# Pi3_Analog_hat.net
KiCad netlist of a schematic drawn in EAGLE
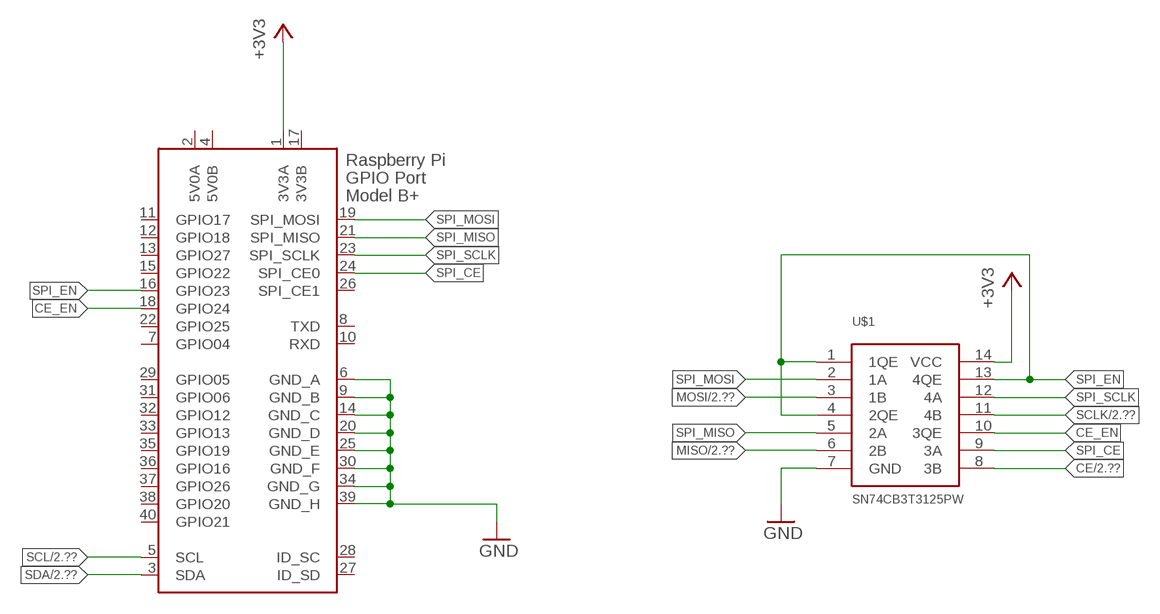
[diagram p0: schematic, sheet 1]
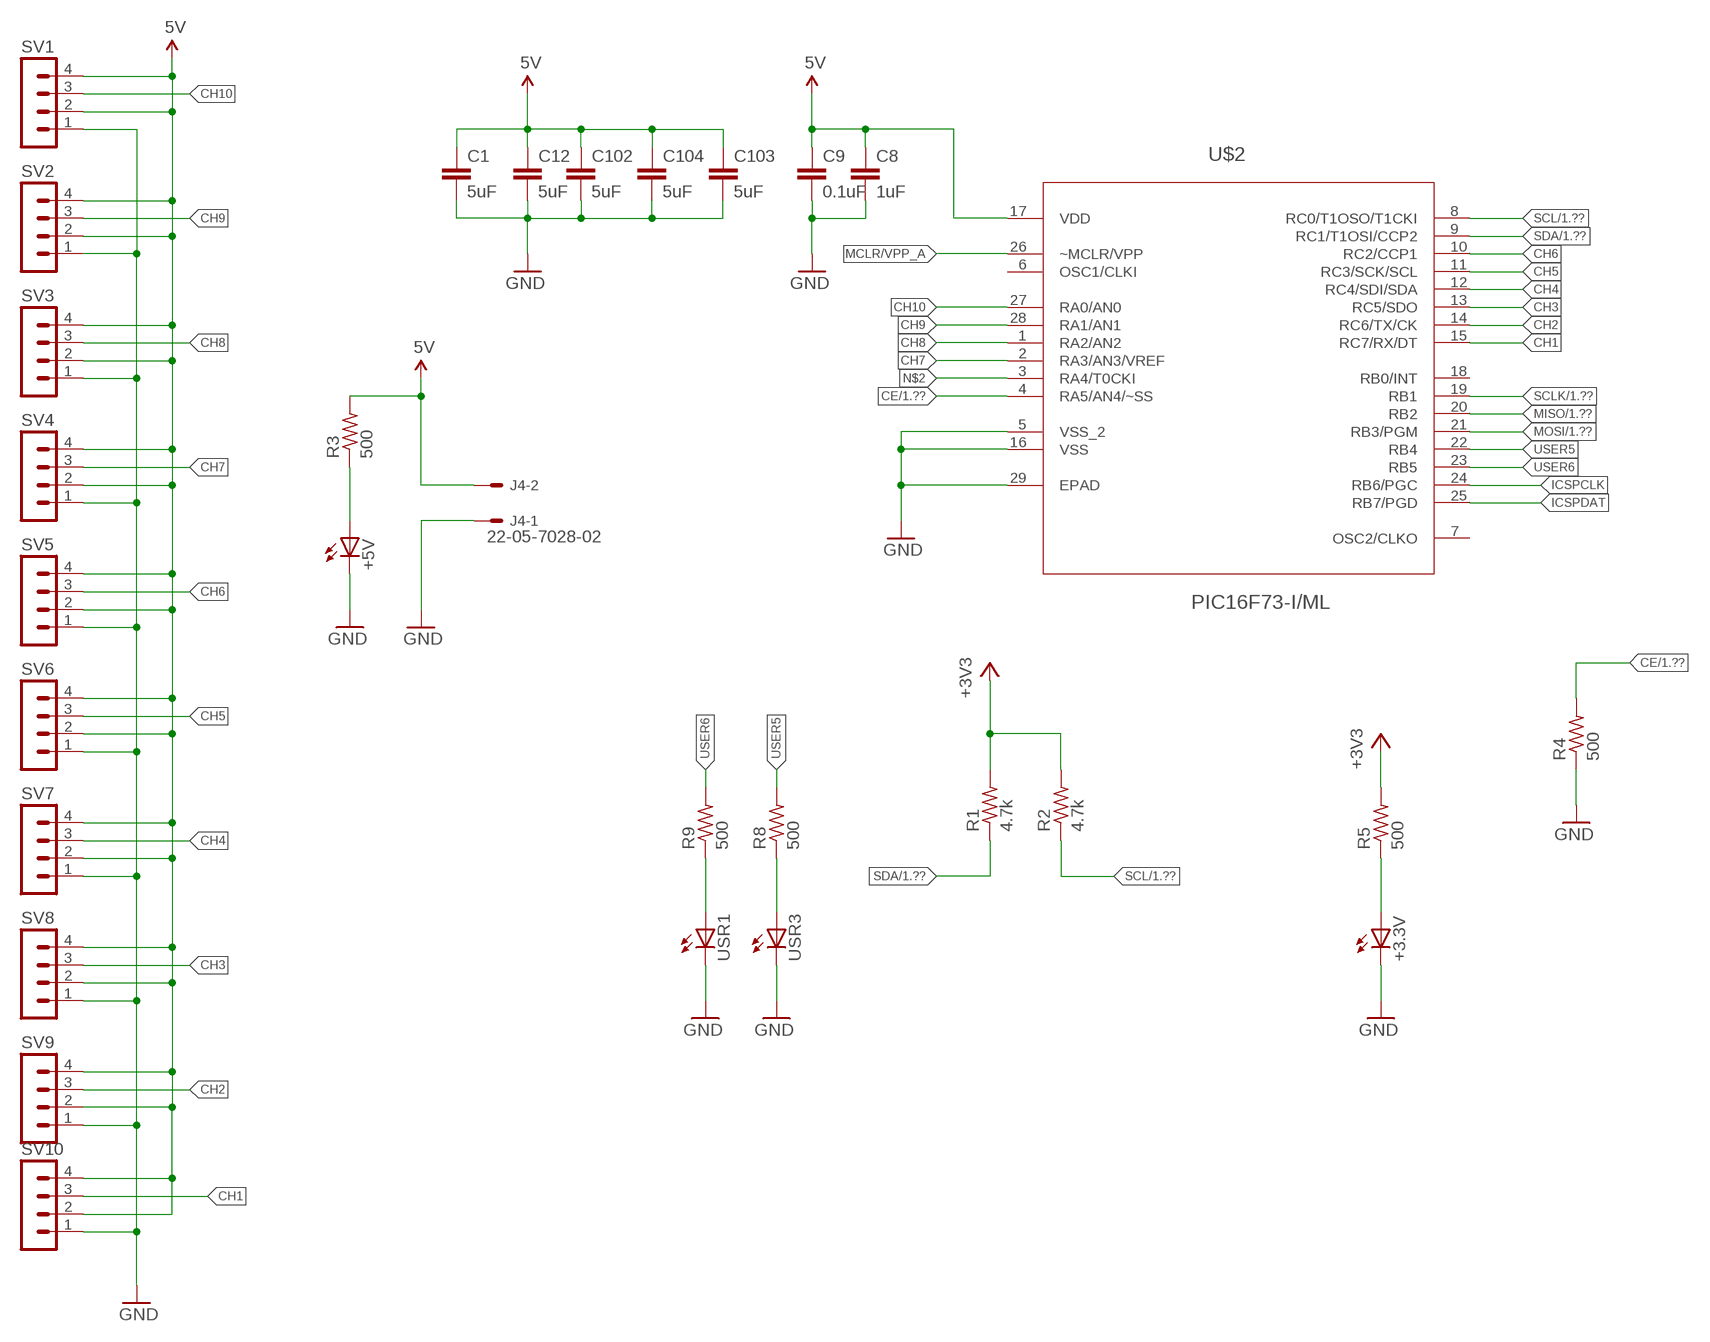
[diagram p1: schematic, sheet 2]

(export (version "E")
  (design (tool "Eeschema 10.0.6"))
  (components
    (comp (ref "+3.3V")
      (value "LEDCHIP-LED0603")
      (footprint "eagle-import:CHIP-LED0603")
      (libsource (lib "eagle-import") (part "LEDCHIP-LED0603"))
    )
    (comp (ref "+5V")
      (value "LEDCHIP-LED0603")
      (footprint "eagle-import:CHIP-LED0603")
      (libsource (lib "eagle-import") (part "LEDCHIP-LED0603"))
    )
    (comp (ref "C1")
      (value "5uF")
      (footprint "eagle-import:C0402")
      (libsource (lib "eagle-import") (part "C-EUC0402"))
    )
    (comp (ref "C8")
      (value "1uF")
      (footprint "eagle-import:C0402")
      (libsource (lib "eagle-import") (part "C-EUC0402"))
    )
    (comp (ref "C9")
      (value "0.1uF")
      (footprint "eagle-import:C0402")
      (libsource (lib "eagle-import") (part "C-EUC0402"))
    )
    (comp (ref "C12")
      (value "5uF")
      (footprint "eagle-import:C0402")
      (libsource (lib "eagle-import") (part "C-EUC0402"))
    )
    (comp (ref "C102")
      (value "5uF")
      (footprint "eagle-import:C0402")
      (libsource (lib "eagle-import") (part "C-EUC0402"))
    )
    (comp (ref "C103")
      (value "5uF")
      (footprint "eagle-import:C0402")
      (libsource (lib "eagle-import") (part "C-EUC0402"))
    )
    (comp (ref "C104")
      (value "5uF")
      (footprint "eagle-import:C0402")
      (libsource (lib "eagle-import") (part "C-EUC0402"))
    )
    (comp (ref "J4")
      (value "22-05-7028-02")
      (footprint "eagle-import:7395-02")
      (libsource (lib "eagle-import") (part "22-?-0205-7028"))
    )
    (comp (ref "R1")
      (value "4.7k")
      (footprint "eagle-import:R0402")
      (libsource (lib "eagle-import") (part "R-US_R0402"))
    )
    (comp (ref "R2")
      (value "4.7k")
      (footprint "eagle-import:R0402")
      (libsource (lib "eagle-import") (part "R-US_R0402"))
    )
    (comp (ref "R3")
      (value "500")
      (footprint "eagle-import:R0402")
      (libsource (lib "eagle-import") (part "R-US_R0402"))
    )
    (comp (ref "R4")
      (value "500")
      (footprint "eagle-import:R0402")
      (libsource (lib "eagle-import") (part "R-US_R0402"))
    )
    (comp (ref "R5")
      (value "500")
      (footprint "eagle-import:R0402")
      (libsource (lib "eagle-import") (part "R-US_R0402"))
    )
    (comp (ref "R8")
      (value "500")
      (footprint "eagle-import:R0402")
      (libsource (lib "eagle-import") (part "R-US_R0402"))
    )
    (comp (ref "R9")
      (value "500")
      (footprint "eagle-import:R0402")
      (libsource (lib "eagle-import") (part "R-US_R0402"))
    )
    (comp (ref "SV1")
      (value "MA04-1")
      (footprint "eagle-import:MA04-1")
      (libsource (lib "eagle-import") (part "MA04-1"))
    )
    (comp (ref "SV2")
      (value "MA04-1")
      (footprint "eagle-import:MA04-1")
      (libsource (lib "eagle-import") (part "MA04-1"))
    )
    (comp (ref "SV3")
      (value "MA04-1")
      (footprint "eagle-import:MA04-1")
      (libsource (lib "eagle-import") (part "MA04-1"))
    )
    (comp (ref "SV4")
      (value "MA04-1")
      (footprint "eagle-import:MA04-1")
      (libsource (lib "eagle-import") (part "MA04-1"))
    )
    (comp (ref "SV5")
      (value "MA04-1")
      (footprint "eagle-import:MA04-1")
      (libsource (lib "eagle-import") (part "MA04-1"))
    )
    (comp (ref "SV6")
      (value "MA04-1")
      (footprint "eagle-import:MA04-1")
      (libsource (lib "eagle-import") (part "MA04-1"))
    )
    (comp (ref "SV7")
      (value "MA04-1")
      (footprint "eagle-import:MA04-1")
      (libsource (lib "eagle-import") (part "MA04-1"))
    )
    (comp (ref "SV8")
      (value "MA04-1")
      (footprint "eagle-import:MA04-1")
      (libsource (lib "eagle-import") (part "MA04-1"))
    )
    (comp (ref "SV9")
      (value "MA04-1")
      (footprint "eagle-import:MA04-1")
      (libsource (lib "eagle-import") (part "MA04-1"))
    )
    (comp (ref "SV10")
      (value "MA04-1")
      (footprint "eagle-import:MA04-1")
      (libsource (lib "eagle-import") (part "MA04-1"))
    )
    (comp (ref "U$2")
      (value "PIC16F73-I/ML")
      (footprint "eagle-import:QFN65P600X600X100-28N")
      (libsource (lib "eagle-import") (part "PIC16F73-I/ML"))
    )
    (comp (ref "USR1")
      (value "LEDCHIP-LED0603")
      (footprint "eagle-import:CHIP-LED0603")
      (libsource (lib "eagle-import") (part "LEDCHIP-LED0603"))
    )
    (comp (ref "USR3")
      (value "LEDCHIP-LED0603")
      (footprint "eagle-import:CHIP-LED0603")
      (libsource (lib "eagle-import") (part "LEDCHIP-LED0603"))
    )
    (comp (ref "U$1")
      (value "SN74CB3T3125PW")
      (footprint "eagle-import:TSSOP-14")
      (libsource (lib "eagle-import") (part "SN74CB3T3125PW"))
    )
    (comp (ref "X1")
      (value "RASPI_BOARD_B+#_HD")
      (footprint "eagle-import:RASPI_BOARD_B+HAT_DF")
      (libsource (lib "eagle-import") (part "RASPI_BOARD_B+#_HD"))
    )
  )
  (nets
    (net (code "1") (name "+3V3") (class "Default")
      (node (ref "R1") (pin "2") (pinfunction "2_2") (pintype "passive"))
      (node (ref "R2") (pin "2") (pinfunction "2_2") (pintype "passive"))
      (node (ref "R5") (pin "2") (pinfunction "2_2") (pintype "passive"))
      (node (ref "U$1") (pin "14") (pinfunction "VCC_14") (pintype "bidirectional"))
      (node (ref "X1") (pin "1") (pinfunction "3V3A_1") (pintype "power_in"))
    )
    (net (code "2") (name "3V3B") (class "Default")
      (node (ref "X1") (pin "17") (pinfunction "3V3B_17") (pintype "power_in"))
    )
    (net (code "3") (name "5V") (class "Default")
      (node (ref "C1") (pin "1") (pinfunction "1_1") (pintype "passive"))
      (node (ref "C102") (pin "1") (pinfunction "1_1") (pintype "passive"))
      (node (ref "C103") (pin "1") (pinfunction "1_1") (pintype "passive"))
      (node (ref "C104") (pin "1") (pinfunction "1_1") (pintype "passive"))
      (node (ref "C12") (pin "1") (pinfunction "1_1") (pintype "passive"))
      (node (ref "C8") (pin "1") (pinfunction "1_1") (pintype "passive"))
      (node (ref "C9") (pin "1") (pinfunction "1_1") (pintype "passive"))
      (node (ref "J4") (pin "2") (pinfunction "S_2") (pintype "passive"))
      (node (ref "R3") (pin "2") (pinfunction "2_2") (pintype "passive"))
      (node (ref "SV1") (pin "2") (pinfunction "2_2") (pintype "passive"))
      (node (ref "SV1") (pin "4") (pinfunction "4_4") (pintype "passive"))
      (node (ref "SV10") (pin "2") (pinfunction "2_2") (pintype "passive"))
      (node (ref "SV10") (pin "4") (pinfunction "4_4") (pintype "passive"))
      (node (ref "SV2") (pin "2") (pinfunction "2_2") (pintype "passive"))
      (node (ref "SV2") (pin "4") (pinfunction "4_4") (pintype "passive"))
      (node (ref "SV3") (pin "2") (pinfunction "2_2") (pintype "passive"))
      (node (ref "SV3") (pin "4") (pinfunction "4_4") (pintype "passive"))
      (node (ref "SV4") (pin "2") (pinfunction "2_2") (pintype "passive"))
      (node (ref "SV4") (pin "4") (pinfunction "4_4") (pintype "passive"))
      (node (ref "SV5") (pin "2") (pinfunction "2_2") (pintype "passive"))
      (node (ref "SV5") (pin "4") (pinfunction "4_4") (pintype "passive"))
      (node (ref "SV6") (pin "2") (pinfunction "2_2") (pintype "passive"))
      (node (ref "SV6") (pin "4") (pinfunction "4_4") (pintype "passive"))
      (node (ref "SV7") (pin "2") (pinfunction "2_2") (pintype "passive"))
      (node (ref "SV7") (pin "4") (pinfunction "4_4") (pintype "passive"))
      (node (ref "SV8") (pin "2") (pinfunction "2_2") (pintype "passive"))
      (node (ref "SV8") (pin "4") (pinfunction "4_4") (pintype "passive"))
      (node (ref "SV9") (pin "2") (pinfunction "2_2") (pintype "passive"))
      (node (ref "SV9") (pin "4") (pinfunction "4_4") (pintype "passive"))
      (node (ref "U$2") (pin "17") (pinfunction "VDD_17") (pintype "power_in"))
    )
    (net (code "4") (name "5V0A") (class "Default")
      (node (ref "X1") (pin "2") (pinfunction "5V0A_2") (pintype "power_in"))
    )
    (net (code "5") (name "5V0B") (class "Default")
      (node (ref "X1") (pin "4") (pinfunction "5V0B_4") (pintype "power_in"))
    )
    (net (code "6") (name "CE") (class "Default")
      (node (ref "R4") (pin "2") (pinfunction "2_2") (pintype "passive"))
      (node (ref "U$1") (pin "8") (pinfunction "3B_8") (pintype "bidirectional"))
      (node (ref "U$2") (pin "4") (pinfunction "RA5/AN4/~{SS}_4") (pintype "bidirectional"))
    )
    (net (code "7") (name "CE_EN") (class "Default")
      (node (ref "U$1") (pin "10") (pinfunction "3QE_10") (pintype "bidirectional"))
      (node (ref "X1") (pin "18") (pinfunction "GPIO24_18") (pintype "bidirectional"))
    )
    (net (code "8") (name "CH1") (class "Default")
      (node (ref "SV10") (pin "3") (pinfunction "3_3") (pintype "passive"))
      (node (ref "U$2") (pin "15") (pinfunction "RC7/RX/DT_15") (pintype "bidirectional"))
    )
    (net (code "9") (name "CH2") (class "Default")
      (node (ref "SV9") (pin "3") (pinfunction "3_3") (pintype "passive"))
      (node (ref "U$2") (pin "14") (pinfunction "RC6/TX/CK_14") (pintype "bidirectional"))
    )
    (net (code "10") (name "CH3") (class "Default")
      (node (ref "SV8") (pin "3") (pinfunction "3_3") (pintype "passive"))
      (node (ref "U$2") (pin "13") (pinfunction "RC5/SDO_13") (pintype "bidirectional"))
    )
    (net (code "11") (name "CH4") (class "Default")
      (node (ref "SV7") (pin "3") (pinfunction "3_3") (pintype "passive"))
      (node (ref "U$2") (pin "12") (pinfunction "RC4/SDI/SDA_12") (pintype "bidirectional"))
    )
    (net (code "12") (name "CH5") (class "Default")
      (node (ref "SV6") (pin "3") (pinfunction "3_3") (pintype "passive"))
      (node (ref "U$2") (pin "11") (pinfunction "RC3/SCK/SCL_11") (pintype "bidirectional"))
    )
    (net (code "13") (name "CH6") (class "Default")
      (node (ref "SV5") (pin "3") (pinfunction "3_3") (pintype "passive"))
      (node (ref "U$2") (pin "10") (pinfunction "RC2/CCP1_10") (pintype "bidirectional"))
    )
    (net (code "14") (name "CH7") (class "Default")
      (node (ref "SV4") (pin "3") (pinfunction "3_3") (pintype "passive"))
      (node (ref "U$2") (pin "2") (pinfunction "RA3/AN3/VREF_2") (pintype "bidirectional"))
    )
    (net (code "15") (name "CH8") (class "Default")
      (node (ref "SV3") (pin "3") (pinfunction "3_3") (pintype "passive"))
      (node (ref "U$2") (pin "1") (pinfunction "RA2/AN2_1") (pintype "bidirectional"))
    )
    (net (code "16") (name "CH9") (class "Default")
      (node (ref "SV2") (pin "3") (pinfunction "3_3") (pintype "passive"))
      (node (ref "U$2") (pin "28") (pinfunction "RA1/AN1_28") (pintype "bidirectional"))
    )
    (net (code "17") (name "CH10") (class "Default")
      (node (ref "SV1") (pin "3") (pinfunction "3_3") (pintype "passive"))
      (node (ref "U$2") (pin "27") (pinfunction "RA0/AN0_27") (pintype "bidirectional"))
    )
    (net (code "18") (name "GND") (class "Default")
      (node (ref "+3.3V") (pin "C") (pinfunction "C_C") (pintype "passive"))
      (node (ref "+5V") (pin "C") (pinfunction "C_C") (pintype "passive"))
      (node (ref "C1") (pin "2") (pinfunction "2_2") (pintype "passive"))
      (node (ref "C102") (pin "2") (pinfunction "2_2") (pintype "passive"))
      (node (ref "C103") (pin "2") (pinfunction "2_2") (pintype "passive"))
      (node (ref "C104") (pin "2") (pinfunction "2_2") (pintype "passive"))
      (node (ref "C12") (pin "2") (pinfunction "2_2") (pintype "passive"))
      (node (ref "C8") (pin "2") (pinfunction "2_2") (pintype "passive"))
      (node (ref "C9") (pin "2") (pinfunction "2_2") (pintype "passive"))
      (node (ref "J4") (pin "1") (pinfunction "S_1") (pintype "passive"))
      (node (ref "R4") (pin "1") (pinfunction "1_1") (pintype "passive"))
      (node (ref "SV1") (pin "1") (pinfunction "1_1") (pintype "passive"))
      (node (ref "SV10") (pin "1") (pinfunction "1_1") (pintype "passive"))
      (node (ref "SV2") (pin "1") (pinfunction "1_1") (pintype "passive"))
      (node (ref "SV3") (pin "1") (pinfunction "1_1") (pintype "passive"))
      (node (ref "SV4") (pin "1") (pinfunction "1_1") (pintype "passive"))
      (node (ref "SV5") (pin "1") (pinfunction "1_1") (pintype "passive"))
      (node (ref "SV6") (pin "1") (pinfunction "1_1") (pintype "passive"))
      (node (ref "SV7") (pin "1") (pinfunction "1_1") (pintype "passive"))
      (node (ref "SV8") (pin "1") (pinfunction "1_1") (pintype "passive"))
      (node (ref "SV9") (pin "1") (pinfunction "1_1") (pintype "passive"))
      (node (ref "U$1") (pin "7") (pinfunction "GND_7") (pintype "bidirectional"))
      (node (ref "U$2") (pin "16") (pinfunction "VSS_16") (pintype "power_in"))
      (node (ref "U$2") (pin "29") (pinfunction "EPAD_29") (pintype "passive"))
      (node (ref "U$2") (pin "5") (pinfunction "VSS_2_5") (pintype "power_in"))
      (node (ref "USR1") (pin "C") (pinfunction "C_C") (pintype "passive"))
      (node (ref "USR3") (pin "C") (pinfunction "C_C") (pintype "passive"))
      (node (ref "X1") (pin "14") (pinfunction "GND_C_14") (pintype "power_in"))
      (node (ref "X1") (pin "20") (pinfunction "GND_D_20") (pintype "power_in"))
      (node (ref "X1") (pin "25") (pinfunction "GND_E_25") (pintype "power_in"))
      (node (ref "X1") (pin "30") (pinfunction "GND_F_30") (pintype "power_in"))
      (node (ref "X1") (pin "34") (pinfunction "GND_G_34") (pintype "power_in"))
      (node (ref "X1") (pin "39") (pinfunction "GND_H_39") (pintype "power_in"))
      (node (ref "X1") (pin "6") (pinfunction "GND_A_6") (pintype "power_in"))
      (node (ref "X1") (pin "9") (pinfunction "GND_B_9") (pintype "power_in"))
    )
    (net (code "19") (name "ICSPCLK") (class "Default")
      (node (ref "U$2") (pin "24") (pinfunction "RB6/PGC_24") (pintype "bidirectional"))
    )
    (net (code "20") (name "ICSPDAT") (class "Default")
      (node (ref "U$2") (pin "25") (pinfunction "RB7/PGD_25") (pintype "bidirectional"))
    )
    (net (code "21") (name "MCLR{slash}VPP_A") (class "Default")
      (node (ref "U$2") (pin "26") (pinfunction "~{MCLR/VPP}_26") (pintype "input"))
    )
    (net (code "22") (name "MISO") (class "Default")
      (node (ref "U$1") (pin "6") (pinfunction "2B_6") (pintype "bidirectional"))
      (node (ref "U$2") (pin "20") (pinfunction "RB2_20") (pintype "bidirectional"))
    )
    (net (code "23") (name "MOSI") (class "Default")
      (node (ref "U$1") (pin "3") (pinfunction "1B_3") (pintype "bidirectional"))
      (node (ref "U$2") (pin "21") (pinfunction "RB3/PGM_21") (pintype "bidirectional"))
    )
    (net (code "24") (name "N$2") (class "Default")
      (node (ref "U$2") (pin "3") (pinfunction "RA4/T0CKI_3") (pintype "bidirectional"))
    )
    (net (code "25") (name "Net-(+3.3V-PadA)") (class "Default")
      (node (ref "+3.3V") (pin "A") (pinfunction "A_A") (pintype "passive"))
      (node (ref "R5") (pin "1") (pinfunction "1_1") (pintype "passive"))
    )
    (net (code "26") (name "Net-(+5V-PadA)") (class "Default")
      (node (ref "+5V") (pin "A") (pinfunction "A_A") (pintype "passive"))
      (node (ref "R3") (pin "1") (pinfunction "1_1") (pintype "passive"))
    )
    (net (code "27") (name "Net-(R8-Pad1)") (class "Default")
      (node (ref "R8") (pin "1") (pinfunction "1_1") (pintype "passive"))
      (node (ref "USR3") (pin "A") (pinfunction "A_A") (pintype "passive"))
    )
    (net (code "28") (name "Net-(R9-Pad1)") (class "Default")
      (node (ref "R9") (pin "1") (pinfunction "1_1") (pintype "passive"))
      (node (ref "USR1") (pin "A") (pinfunction "A_A") (pintype "passive"))
    )
    (net (code "29") (name "SCL") (class "Default")
      (node (ref "R2") (pin "1") (pinfunction "1_1") (pintype "passive"))
      (node (ref "U$2") (pin "8") (pinfunction "RC0/T1OSO/T1CKI_8") (pintype "bidirectional"))
      (node (ref "X1") (pin "5") (pinfunction "SCL_5") (pintype "bidirectional"))
    )
    (net (code "30") (name "SCLK") (class "Default")
      (node (ref "U$1") (pin "11") (pinfunction "4B_11") (pintype "bidirectional"))
      (node (ref "U$2") (pin "19") (pinfunction "RB1_19") (pintype "bidirectional"))
    )
    (net (code "31") (name "SDA") (class "Default")
      (node (ref "R1") (pin "1") (pinfunction "1_1") (pintype "passive"))
      (node (ref "U$2") (pin "9") (pinfunction "RC1/T1OSI/CCP2_9") (pintype "bidirectional"))
      (node (ref "X1") (pin "3") (pinfunction "SDA_3") (pintype "bidirectional"))
    )
    (net (code "32") (name "SPI_CE") (class "Default")
      (node (ref "U$1") (pin "9") (pinfunction "3A_9") (pintype "bidirectional"))
      (node (ref "X1") (pin "24") (pinfunction "SPI_CE0_24") (pintype "bidirectional"))
    )
    (net (code "33") (name "SPI_EN") (class "Default")
      (node (ref "U$1") (pin "1") (pinfunction "1QE_1") (pintype "bidirectional"))
      (node (ref "U$1") (pin "13") (pinfunction "4QE_13") (pintype "bidirectional"))
      (node (ref "U$1") (pin "4") (pinfunction "2QE_4") (pintype "bidirectional"))
      (node (ref "X1") (pin "16") (pinfunction "GPIO23_16") (pintype "bidirectional"))
    )
    (net (code "34") (name "SPI_MISO") (class "Default")
      (node (ref "U$1") (pin "5") (pinfunction "2A_5") (pintype "bidirectional"))
      (node (ref "X1") (pin "21") (pinfunction "SPI_MISO_21") (pintype "bidirectional"))
    )
    (net (code "35") (name "SPI_MOSI") (class "Default")
      (node (ref "U$1") (pin "2") (pinfunction "1A_2") (pintype "bidirectional"))
      (node (ref "X1") (pin "19") (pinfunction "SPI_MOSI_19") (pintype "bidirectional"))
    )
    (net (code "36") (name "SPI_SCLK") (class "Default")
      (node (ref "U$1") (pin "12") (pinfunction "4A_12") (pintype "bidirectional"))
      (node (ref "X1") (pin "23") (pinfunction "SPI_SCLK_23") (pintype "bidirectional"))
    )
    (net (code "37") (name "USER5") (class "Default")
      (node (ref "R8") (pin "2") (pinfunction "2_2") (pintype "passive"))
      (node (ref "U$2") (pin "22") (pinfunction "RB4_22") (pintype "bidirectional"))
    )
    (net (code "38") (name "USER6") (class "Default")
      (node (ref "R9") (pin "2") (pinfunction "2_2") (pintype "passive"))
      (node (ref "U$2") (pin "23") (pinfunction "RB5_23") (pintype "bidirectional"))
    )
    (net (code "39") (name "unconnected-(U$2-OSC1{slash}CLKI-Pad6)") (class "Default")
      (node (ref "U$2") (pin "6") (pinfunction "OSC1/CLKI_6") (pintype "input"))
    )
    (net (code "40") (name "unconnected-(U$2-OSC2{slash}CLKO-Pad7)") (class "Default")
      (node (ref "U$2") (pin "7") (pinfunction "OSC2/CLKO_7") (pintype "output"))
    )
    (net (code "41") (name "unconnected-(U$2-RB0{slash}INT-Pad18)") (class "Default")
      (node (ref "U$2") (pin "18") (pinfunction "RB0/INT_18") (pintype "bidirectional"))
    )
    (net (code "42") (name "unconnected-(X1-GPIO04-Pad7)") (class "Default")
      (node (ref "X1") (pin "7") (pinfunction "GPIO04_7") (pintype "bidirectional"))
    )
    (net (code "43") (name "unconnected-(X1-GPIO05-Pad29)") (class "Default")
      (node (ref "X1") (pin "29") (pinfunction "GPIO05_29") (pintype "no_connect"))
    )
    (net (code "44") (name "unconnected-(X1-GPIO06-Pad31)") (class "Default")
      (node (ref "X1") (pin "31") (pinfunction "GPIO06_31") (pintype "no_connect"))
    )
    (net (code "45") (name "unconnected-(X1-GPIO12-Pad32)") (class "Default")
      (node (ref "X1") (pin "32") (pinfunction "GPIO12_32") (pintype "no_connect"))
    )
    (net (code "46") (name "unconnected-(X1-GPIO13-Pad33)") (class "Default")
      (node (ref "X1") (pin "33") (pinfunction "GPIO13_33") (pintype "no_connect"))
    )
    (net (code "47") (name "unconnected-(X1-GPIO16-Pad36)") (class "Default")
      (node (ref "X1") (pin "36") (pinfunction "GPIO16_36") (pintype "no_connect"))
    )
    (net (code "48") (name "unconnected-(X1-GPIO17-Pad11)") (class "Default")
      (node (ref "X1") (pin "11") (pinfunction "GPIO17_11") (pintype "bidirectional"))
    )
    (net (code "49") (name "unconnected-(X1-GPIO18-Pad12)") (class "Default")
      (node (ref "X1") (pin "12") (pinfunction "GPIO18_12") (pintype "bidirectional"))
    )
    (net (code "50") (name "unconnected-(X1-GPIO19-Pad35)") (class "Default")
      (node (ref "X1") (pin "35") (pinfunction "GPIO19_35") (pintype "no_connect"))
    )
    (net (code "51") (name "unconnected-(X1-GPIO20-Pad38)") (class "Default")
      (node (ref "X1") (pin "38") (pinfunction "GPIO20_38") (pintype "no_connect"))
    )
    (net (code "52") (name "unconnected-(X1-GPIO21-Pad40)") (class "Default")
      (node (ref "X1") (pin "40") (pinfunction "GPIO21_40") (pintype "no_connect"))
    )
    (net (code "53") (name "unconnected-(X1-GPIO22-Pad15)") (class "Default")
      (node (ref "X1") (pin "15") (pinfunction "GPIO22_15") (pintype "bidirectional"))
    )
    (net (code "54") (name "unconnected-(X1-GPIO25-Pad22)") (class "Default")
      (node (ref "X1") (pin "22") (pinfunction "GPIO25_22") (pintype "bidirectional"))
    )
    (net (code "55") (name "unconnected-(X1-GPIO26-Pad37)") (class "Default")
      (node (ref "X1") (pin "37") (pinfunction "GPIO26_37") (pintype "no_connect"))
    )
    (net (code "56") (name "unconnected-(X1-GPIO27-Pad13)") (class "Default")
      (node (ref "X1") (pin "13") (pinfunction "GPIO27_13") (pintype "bidirectional"))
    )
    (net (code "57") (name "unconnected-(X1-ID_SC-Pad28)") (class "Default")
      (node (ref "X1") (pin "28") (pinfunction "ID_SC_28") (pintype "no_connect"))
    )
    (net (code "58") (name "unconnected-(X1-ID_SD-Pad27)") (class "Default")
      (node (ref "X1") (pin "27") (pinfunction "ID_SD_27") (pintype "no_connect"))
    )
    (net (code "59") (name "unconnected-(X1-RXD-Pad10)") (class "Default")
      (node (ref "X1") (pin "10") (pinfunction "RXD_10") (pintype "bidirectional"))
    )
    (net (code "60") (name "unconnected-(X1-SPI_CE1-Pad26)") (class "Default")
      (node (ref "X1") (pin "26") (pinfunction "SPI_CE1_26") (pintype "bidirectional"))
    )
    (net (code "61") (name "unconnected-(X1-TXD-Pad8)") (class "Default")
      (node (ref "X1") (pin "8") (pinfunction "TXD_8") (pintype "bidirectional"))
    )
  )
)
